# bbiq_prototype.net
KiCad netlist of a schematic drawn in EAGLE
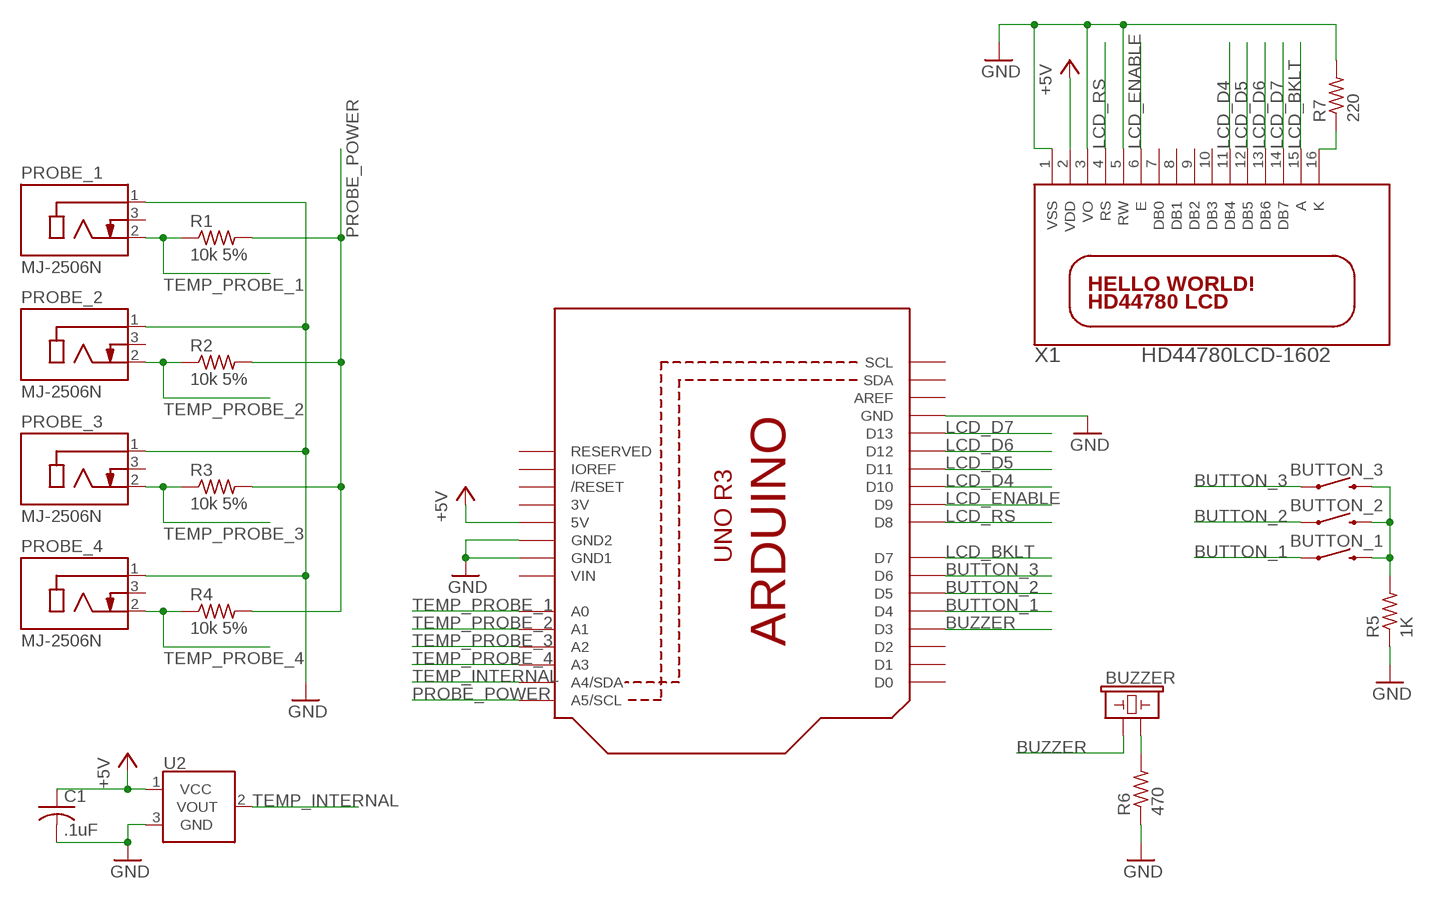
[diagram p0: schematic, sheet 1]

(export (version "E")
  (design (tool "Eeschema 10.0.6"))
  (components
    (comp (ref "BUTTON_1")
      (value "MOMENTARY-SWITCH-SPST-PTH-12MM")
      (footprint "eagle-import:TACTILE_SWITCH_PTH_12MM")
      (libsource (lib "eagle-import") (part "MOMENTARY-SWITCH-SPST-PTH-12MM"))
    )
    (comp (ref "BUTTON_2")
      (value "MOMENTARY-SWITCH-SPST-PTH-12MM")
      (footprint "eagle-import:TACTILE_SWITCH_PTH_12MM")
      (libsource (lib "eagle-import") (part "MOMENTARY-SWITCH-SPST-PTH-12MM"))
    )
    (comp (ref "BUTTON_3")
      (value "MOMENTARY-SWITCH-SPST-PTH-12MM")
      (footprint "eagle-import:TACTILE_SWITCH_PTH_12MM")
      (libsource (lib "eagle-import") (part "MOMENTARY-SWITCH-SPST-PTH-12MM"))
    )
    (comp (ref "BUZZER")
      (value "BUZZER-PTH")
      (footprint "eagle-import:BUZZER-12MM")
      (libsource (lib "eagle-import") (part "BUZZER-PTH"))
    )
    (comp (ref "C1")
      (value ".1uF")
      (footprint "eagle-import:C025-025X050")
      (libsource (lib "eagle-import") (part "C-US025-025X050"))
    )
    (comp (ref "PROBE_1")
      (value "MJ-2506N")
      (footprint "eagle-import:CUI_MJ-2506N")
      (fields (field (name "MANUFACTURER") "CUI INC"))
      (libsource (lib "eagle-import") (part "MJ-2506N"))
    )
    (comp (ref "PROBE_2")
      (value "MJ-2506N")
      (footprint "eagle-import:CUI_MJ-2506N")
      (fields (field (name "MANUFACTURER") "CUI INC"))
      (libsource (lib "eagle-import") (part "MJ-2506N"))
    )
    (comp (ref "PROBE_3")
      (value "MJ-2506N")
      (footprint "eagle-import:CUI_MJ-2506N")
      (fields (field (name "MANUFACTURER") "CUI INC"))
      (libsource (lib "eagle-import") (part "MJ-2506N"))
    )
    (comp (ref "PROBE_4")
      (value "MJ-2506N")
      (footprint "eagle-import:CUI_MJ-2506N")
      (fields (field (name "MANUFACTURER") "CUI INC"))
      (libsource (lib "eagle-import") (part "MJ-2506N"))
    )
    (comp (ref "R1")
      (value "10k 5%")
      (footprint "eagle-import:0207_10")
      (libsource (lib "eagle-import") (part "R-US_0207/10"))
    )
    (comp (ref "R2")
      (value "10k 5%")
      (footprint "eagle-import:0207_10")
      (libsource (lib "eagle-import") (part "R-US_0207/10"))
    )
    (comp (ref "R3")
      (value "10k 5%")
      (footprint "eagle-import:0207_10")
      (libsource (lib "eagle-import") (part "R-US_0207/10"))
    )
    (comp (ref "R4")
      (value "10k 5%")
      (footprint "eagle-import:0207_10")
      (libsource (lib "eagle-import") (part "R-US_0207/10"))
    )
    (comp (ref "R5")
      (value "1K")
      (footprint "eagle-import:0207_10")
      (libsource (lib "eagle-import") (part "R-US_0207/10"))
    )
    (comp (ref "R6")
      (value "470")
      (footprint "eagle-import:0207_10")
      (libsource (lib "eagle-import") (part "R-US_0207/10"))
    )
    (comp (ref "R7")
      (value "220")
      (footprint "eagle-import:0207_10")
      (libsource (lib "eagle-import") (part "R-US_0207/10"))
    )
    (comp (ref "U1")
      (value "ARDUINOR3-BPLACE")
      (footprint "eagle-import:ARDUINOR3-BPLACE")
      (libsource (lib "eagle-import") (part "ARDUINOR3-BPLACE"))
    )
    (comp (ref "U2")
      (value "TMP36GT9")
      (footprint "eagle-import:TO-92")
      (libsource (lib "eagle-import") (part "TMP36GT9"))
    )
    (comp (ref "X1")
      (value "HD44780LCD-1602")
      (footprint "eagle-import:LCD1602")
      (libsource (lib "eagle-import") (part "HD44780LCD-1602"))
    )
  )
  (nets
    (net (code "1") (name "+5V") (class "Default")
      (node (ref "C1") (pin "1") (pinfunction "1_1") (pintype "passive"))
      (node (ref "U1") (pin "5V") (pinfunction "5V_5V") (pintype "power_in"))
      (node (ref "U2") (pin "1") (pinfunction "VCC_1") (pintype "bidirectional"))
      (node (ref "X1") (pin "2") (pinfunction "VDD_2") (pintype "power_in"))
    )
    (net (code "2") (name "/3V") (class "Default")
      (node (ref "U1") (pin "3V") (pinfunction "3V_3V") (pintype "power_in"))
    )
    (net (code "3") (name "/BUTTON_1") (class "Default")
      (node (ref "BUTTON_1") (pin "1") (pinfunction "1_1") (pintype "passive"))
      (node (ref "U1") (pin "D4") (pinfunction "D4_D4") (pintype "bidirectional"))
    )
    (net (code "4") (name "/BUTTON_2") (class "Default")
      (node (ref "BUTTON_2") (pin "1") (pinfunction "1_1") (pintype "passive"))
      (node (ref "U1") (pin "D5") (pinfunction "D5_D5") (pintype "bidirectional"))
    )
    (net (code "5") (name "/BUTTON_3") (class "Default")
      (node (ref "BUTTON_3") (pin "1") (pinfunction "1_1") (pintype "passive"))
      (node (ref "U1") (pin "D6") (pinfunction "D6_D6") (pintype "bidirectional"))
    )
    (net (code "6") (name "/BUZZER") (class "Default")
      (node (ref "BUZZER") (pin "+") (pinfunction "1_+") (pintype "passive"))
      (node (ref "U1") (pin "D3") (pinfunction "D3_D3") (pintype "bidirectional"))
    )
    (net (code "7") (name "/LCD_BKLT") (class "Default")
      (node (ref "U1") (pin "D7") (pinfunction "D7_D7") (pintype "bidirectional"))
      (node (ref "X1") (pin "15") (pinfunction "A_15") (pintype "input"))
    )
    (net (code "8") (name "/LCD_D4") (class "Default")
      (node (ref "U1") (pin "D10") (pinfunction "D10_D10") (pintype "bidirectional"))
      (node (ref "X1") (pin "11") (pinfunction "DB4_11") (pintype "bidirectional"))
    )
    (net (code "9") (name "/LCD_D5") (class "Default")
      (node (ref "U1") (pin "D11") (pinfunction "D11_D11") (pintype "bidirectional"))
      (node (ref "X1") (pin "12") (pinfunction "DB5_12") (pintype "bidirectional"))
    )
    (net (code "10") (name "/LCD_D6") (class "Default")
      (node (ref "U1") (pin "D12") (pinfunction "D12_D12") (pintype "bidirectional"))
      (node (ref "X1") (pin "13") (pinfunction "DB6_13") (pintype "bidirectional"))
    )
    (net (code "11") (name "/LCD_D7") (class "Default")
      (node (ref "U1") (pin "D13") (pinfunction "D13_D13") (pintype "bidirectional"))
      (node (ref "X1") (pin "14") (pinfunction "DB7_14") (pintype "bidirectional"))
    )
    (net (code "12") (name "/LCD_ENABLE") (class "Default")
      (node (ref "U1") (pin "D9") (pinfunction "D9_D9") (pintype "bidirectional"))
      (node (ref "X1") (pin "6") (pinfunction "E_6") (pintype "input"))
    )
    (net (code "13") (name "/LCD_RS") (class "Default")
      (node (ref "U1") (pin "D8") (pinfunction "D8_D8") (pintype "bidirectional"))
      (node (ref "X1") (pin "4") (pinfunction "RS_4") (pintype "input"))
    )
    (net (code "14") (name "/PROBE_POWER") (class "Default")
      (node (ref "R1") (pin "2") (pinfunction "2_2") (pintype "passive"))
      (node (ref "R2") (pin "2") (pinfunction "2_2") (pintype "passive"))
      (node (ref "R3") (pin "2") (pinfunction "2_2") (pintype "passive"))
      (node (ref "R4") (pin "2") (pinfunction "2_2") (pintype "passive"))
      (node (ref "U1") (pin "A5") (pinfunction "A5/SCL_A5") (pintype "bidirectional"))
    )
    (net (code "15") (name "/TEMP_INTERNAL") (class "Default")
      (node (ref "U1") (pin "A4") (pinfunction "A4/SDA_A4") (pintype "bidirectional"))
      (node (ref "U2") (pin "2") (pinfunction "VOUT_2") (pintype "bidirectional"))
    )
    (net (code "16") (name "/TEMP_PROBE_1") (class "Default")
      (node (ref "PROBE_1") (pin "2") (pinfunction "2_2") (pintype "passive"))
      (node (ref "R1") (pin "1") (pinfunction "1_1") (pintype "passive"))
      (node (ref "U1") (pin "A0") (pinfunction "A0_A0") (pintype "bidirectional"))
    )
    (net (code "17") (name "/TEMP_PROBE_2") (class "Default")
      (node (ref "PROBE_2") (pin "2") (pinfunction "2_2") (pintype "passive"))
      (node (ref "R2") (pin "1") (pinfunction "1_1") (pintype "passive"))
      (node (ref "U1") (pin "A1") (pinfunction "A1_A1") (pintype "bidirectional"))
    )
    (net (code "18") (name "/TEMP_PROBE_3") (class "Default")
      (node (ref "PROBE_3") (pin "2") (pinfunction "2_2") (pintype "passive"))
      (node (ref "R3") (pin "1") (pinfunction "1_1") (pintype "passive"))
      (node (ref "U1") (pin "A2") (pinfunction "A2_A2") (pintype "bidirectional"))
    )
    (net (code "19") (name "/TEMP_PROBE_4") (class "Default")
      (node (ref "PROBE_4") (pin "2") (pinfunction "2_2") (pintype "passive"))
      (node (ref "R4") (pin "1") (pinfunction "1_1") (pintype "passive"))
      (node (ref "U1") (pin "A3") (pinfunction "A3_A3") (pintype "bidirectional"))
    )
    (net (code "20") (name "/VIN") (class "Default")
      (node (ref "U1") (pin "VIN") (pinfunction "VIN_VIN") (pintype "power_in"))
    )
    (net (code "21") (name "GND") (class "Default")
      (node (ref "C1") (pin "2") (pinfunction "2_2") (pintype "passive"))
      (node (ref "PROBE_1") (pin "1") (pinfunction "1_1") (pintype "passive"))
      (node (ref "PROBE_2") (pin "1") (pinfunction "1_1") (pintype "passive"))
      (node (ref "PROBE_3") (pin "1") (pinfunction "1_1") (pintype "passive"))
      (node (ref "PROBE_4") (pin "1") (pinfunction "1_1") (pintype "passive"))
      (node (ref "R5") (pin "1") (pinfunction "1_1") (pintype "passive"))
      (node (ref "R6") (pin "1") (pinfunction "1_1") (pintype "passive"))
      (node (ref "R7") (pin "2") (pinfunction "2_2") (pintype "passive"))
      (node (ref "U1") (pin "GND") (pinfunction "GND_GND") (pintype "power_in"))
      (node (ref "U1") (pin "GND1") (pinfunction "GND1_GND1") (pintype "power_in"))
      (node (ref "U1") (pin "GND2") (pinfunction "GND2_GND2") (pintype "power_in"))
      (node (ref "U2") (pin "3") (pinfunction "GND_3") (pintype "bidirectional"))
      (node (ref "X1") (pin "1") (pinfunction "VSS_1") (pintype "power_in"))
      (node (ref "X1") (pin "3") (pinfunction "VO_3") (pintype "input"))
      (node (ref "X1") (pin "5") (pinfunction "RW_5") (pintype "input"))
    )
    (net (code "22") (name "Net-(BUTTON_1-2)") (class "Default")
      (node (ref "BUTTON_1") (pin "3") (pinfunction "2_3") (pintype "passive"))
      (node (ref "BUTTON_2") (pin "3") (pinfunction "2_3") (pintype "passive"))
      (node (ref "BUTTON_3") (pin "3") (pinfunction "2_3") (pintype "passive"))
      (node (ref "R5") (pin "2") (pinfunction "2_2") (pintype "passive"))
    )
    (net (code "23") (name "Net-(BUZZER-2)") (class "Default")
      (node (ref "BUZZER") (pin "-") (pinfunction "2_-") (pintype "passive"))
      (node (ref "R6") (pin "2") (pinfunction "2_2") (pintype "passive"))
    )
    (net (code "24") (name "Net-(X1-K)") (class "Default")
      (node (ref "R7") (pin "1") (pinfunction "1_1") (pintype "passive"))
      (node (ref "X1") (pin "16") (pinfunction "K_16") (pintype "input"))
    )
    (net (code "25") (name "unconnected-(PROBE_1-Pad3)") (class "Default")
      (node (ref "PROBE_1") (pin "3") (pinfunction "3_3") (pintype "passive"))
    )
    (net (code "26") (name "unconnected-(PROBE_2-Pad3)") (class "Default")
      (node (ref "PROBE_2") (pin "3") (pinfunction "3_3") (pintype "passive"))
    )
    (net (code "27") (name "unconnected-(PROBE_3-Pad3)") (class "Default")
      (node (ref "PROBE_3") (pin "3") (pinfunction "3_3") (pintype "passive"))
    )
    (net (code "28") (name "unconnected-(PROBE_4-Pad3)") (class "Default")
      (node (ref "PROBE_4") (pin "3") (pinfunction "3_3") (pintype "passive"))
    )
    (net (code "29") (name "unconnected-(U1-PadAREF)") (class "Default")
      (node (ref "U1") (pin "AREF") (pinfunction "AREF_AREF") (pintype "bidirectional"))
    )
    (net (code "30") (name "unconnected-(U1-PadD0)") (class "Default")
      (node (ref "U1") (pin "D0") (pinfunction "D0_D0") (pintype "bidirectional"))
    )
    (net (code "31") (name "unconnected-(U1-PadD1)") (class "Default")
      (node (ref "U1") (pin "D1") (pinfunction "D1_D1") (pintype "bidirectional"))
    )
    (net (code "32") (name "unconnected-(U1-PadD2)") (class "Default")
      (node (ref "U1") (pin "D2") (pinfunction "D2_D2") (pintype "bidirectional"))
    )
    (net (code "33") (name "unconnected-(U1-PadIOREF)") (class "Default")
      (node (ref "U1") (pin "IOREF") (pinfunction "IOREF_IOREF") (pintype "output"))
    )
    (net (code "34") (name "unconnected-(U1-PadRESERVED)") (class "Default")
      (node (ref "U1") (pin "RESERVED") (pinfunction "RESERVED_RESERVED") (pintype "no_connect"))
    )
    (net (code "35") (name "unconnected-(U1-PadSCL)") (class "Default")
      (node (ref "U1") (pin "SCL") (pinfunction "SCL_SCL") (pintype "bidirectional"))
    )
    (net (code "36") (name "unconnected-(U1-PadSDA)") (class "Default")
      (node (ref "U1") (pin "SDA") (pinfunction "SDA_SDA") (pintype "bidirectional"))
    )
    (net (code "37") (name "unconnected-(U1-{slash}RESET-PadRESET)") (class "Default")
      (node (ref "U1") (pin "RESET") (pinfunction "/RESET_RESET") (pintype "bidirectional"))
    )
    (net (code "38") (name "unconnected-(X1-DB0-Pad7)") (class "Default")
      (node (ref "X1") (pin "7") (pinfunction "DB0_7") (pintype "bidirectional"))
    )
    (net (code "39") (name "unconnected-(X1-DB1-Pad8)") (class "Default")
      (node (ref "X1") (pin "8") (pinfunction "DB1_8") (pintype "bidirectional"))
    )
    (net (code "40") (name "unconnected-(X1-DB2-Pad9)") (class "Default")
      (node (ref "X1") (pin "9") (pinfunction "DB2_9") (pintype "bidirectional"))
    )
    (net (code "41") (name "unconnected-(X1-DB3-Pad10)") (class "Default")
      (node (ref "X1") (pin "10") (pinfunction "DB3_10") (pintype "bidirectional"))
    )
  )
)
